# Driver_Morpheus_SENSOR_CORRENTE.net
KiCad netlist of a schematic drawn in Altium Designer
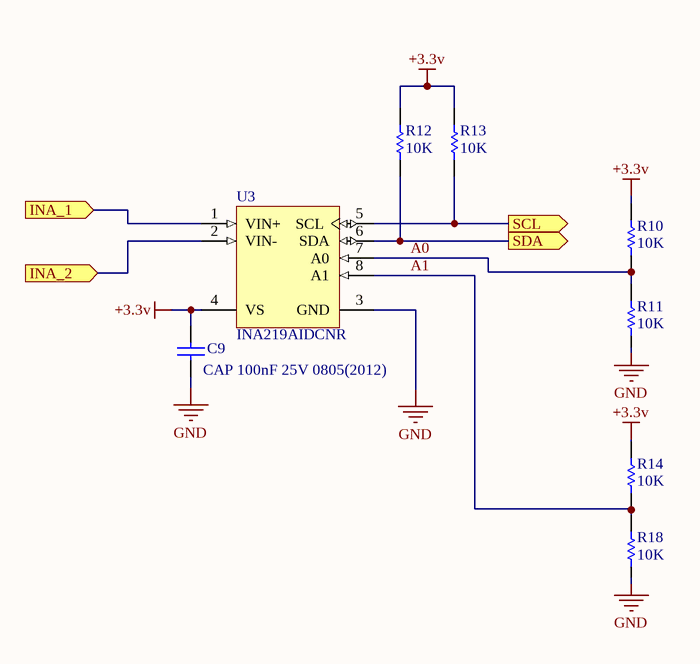
[diagram p0: Driver Morpheus SENSOR CORRENTE.SchDoc]

(export (version "E")
  (design (tool "Eeschema 10.0.6"))
  (components
    (comp (ref "C9")
      (value "CAP 100nF 25V 0805(2012)")
      (footprint "CAPC0805(2012)145_M")
      (description "CAP 100nF 25V ±5% 0805 (2012 Metric) Thickness 1.45mm SMD")
      (fields (field (name "TOLERANCE") "Â±5%"))
      (libsource (lib "Altium Content Vault") (part "CAP"))
    )
    (comp (ref "R10")
      (value "10K")
      (footprint "RES-0402")
      (description "RES SMD 1K OHM 5% 1/16W 0402")
      (fields (field (name "Comment") "RC0402JR-071KL"))
      (libsource (lib "Schlib1") (part "RES 1K 0402"))
    )
    (comp (ref "R11")
      (value "10K")
      (footprint "RES-0402")
      (description "RES SMD 1K OHM 5% 1/16W 0402")
      (fields (field (name "Comment") "RC0402JR-071KL"))
      (libsource (lib "Schlib1") (part "RES 1K 0402"))
    )
    (comp (ref "R12")
      (value "10K")
      (footprint "RES-0402")
      (description "RES SMD 1K OHM 5% 1/16W 0402")
      (fields (field (name "Comment") "RC0402JR-071KL"))
      (libsource (lib "Schlib1") (part "RES 1K 0402"))
    )
    (comp (ref "R13")
      (value "10K")
      (footprint "RES-0402")
      (description "RES SMD 1K OHM 5% 1/16W 0402")
      (fields (field (name "Comment") "RC0402JR-071KL"))
      (libsource (lib "Schlib1") (part "RES 1K 0402"))
    )
    (comp (ref "R14")
      (value "10K")
      (footprint "RES-0402")
      (description "RES SMD 1K OHM 5% 1/16W 0402")
      (fields (field (name "Comment") "RC0402JR-071KL"))
      (libsource (lib "Schlib1") (part "RES 1K 0402"))
    )
    (comp (ref "R18")
      (value "10K")
      (footprint "RES-0402")
      (description "RES SMD 1K OHM 5% 1/16W 0402")
      (fields (field (name "Comment") "RC0402JR-071KL"))
      (libsource (lib "Schlib1") (part "RES 1K 0402"))
    )
    (comp (ref "U3")
      (value "INA219AIDCNR")
      (footprint "DCN0008A_M")
      (fields (field (name "MANUFACTURER") "Texas Instruments"))
      (libsource (lib "Altium Content Vault") (part "TI-INA219DCN8"))
    )
  )
  (nets
    (net (code "1") (name "+3.3v") (class "Default")
      (node (ref "C9") (pin "2") (pinfunction "2_2") (pintype "passive"))
      (node (ref "R10") (pin "2") (pinfunction "2_2") (pintype "passive"))
      (node (ref "R12") (pin "2") (pinfunction "2_2") (pintype "passive"))
      (node (ref "R13") (pin "2") (pinfunction "2_2") (pintype "passive"))
      (node (ref "R14") (pin "2") (pinfunction "2_2") (pintype "passive"))
      (node (ref "U3") (pin "4") (pinfunction "VS_4") (pintype "power_in"))
    )
    (net (code "2") (name "/A0") (class "Default")
      (node (ref "R10") (pin "1") (pinfunction "1_1") (pintype "passive"))
      (node (ref "R11") (pin "2") (pinfunction "2_2") (pintype "passive"))
      (node (ref "U3") (pin "7") (pinfunction "A0_7") (pintype "input"))
    )
    (net (code "3") (name "/A1") (class "Default")
      (node (ref "R14") (pin "1") (pinfunction "1_1") (pintype "passive"))
      (node (ref "R18") (pin "2") (pinfunction "2_2") (pintype "passive"))
      (node (ref "U3") (pin "8") (pinfunction "A1_8") (pintype "input"))
    )
    (net (code "4") (name "/INA_1") (class "Default")
      (node (ref "U3") (pin "1") (pinfunction "VIN+_1") (pintype "input"))
    )
    (net (code "5") (name "/INA_2") (class "Default")
      (node (ref "U3") (pin "2") (pinfunction "VIN-_2") (pintype "input"))
    )
    (net (code "6") (name "/SCL") (class "Default")
      (node (ref "R13") (pin "1") (pinfunction "1_1") (pintype "passive"))
      (node (ref "U3") (pin "5") (pinfunction "SCL_5") (pintype "bidirectional"))
    )
    (net (code "7") (name "/SDA") (class "Default")
      (node (ref "R12") (pin "1") (pinfunction "1_1") (pintype "passive"))
      (node (ref "U3") (pin "6") (pinfunction "SDA_6") (pintype "bidirectional"))
    )
    (net (code "8") (name "GND") (class "Default")
      (node (ref "C9") (pin "1") (pinfunction "1_1") (pintype "passive"))
      (node (ref "R11") (pin "1") (pinfunction "1_1") (pintype "passive"))
      (node (ref "R18") (pin "1") (pinfunction "1_1") (pintype "passive"))
      (node (ref "U3") (pin "3") (pinfunction "GND_3") (pintype "power_in"))
    )
  )
)
